# TX.net
KiCad netlist of a schematic drawn in EAGLE
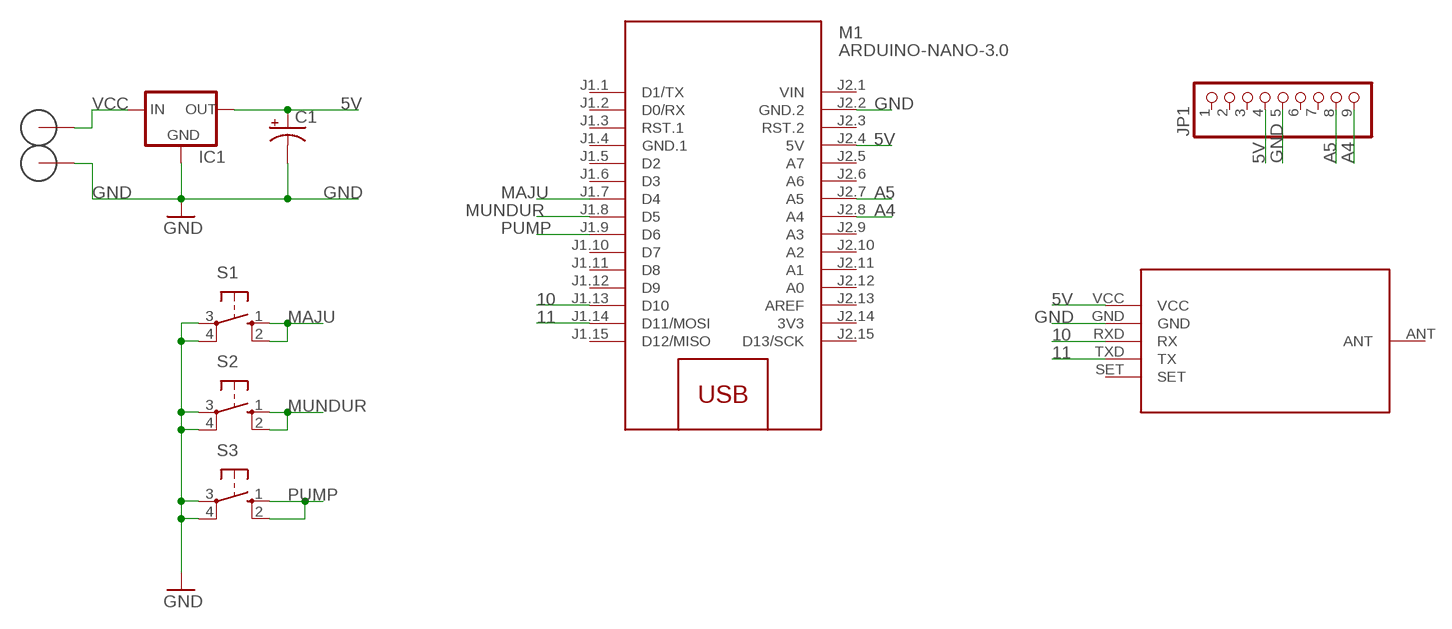
[diagram p0: schematic, sheet 1]

(export (version "E")
  (design (tool "Eeschema 10.0.6"))
  (components
    (comp (ref "C1")
      (value "CPOL-USE2.5-7")
      (footprint "eagle-import:E2,5-7")
      (libsource (lib "eagle-import") (part "CPOL-USE2.5-7"))
    )
    (comp (ref "H1")
      (value "3MM_HOLE")
      (footprint "eagle-import:3MM_HOLE")
      (libsource (lib "eagle-import") (part "3MM_HOLE"))
    )
    (comp (ref "H2")
      (value "3MM_HOLE")
      (footprint "eagle-import:3MM_HOLE")
      (libsource (lib "eagle-import") (part "3MM_HOLE"))
    )
    (comp (ref "IC1")
      (value "78XXS")
      (footprint "eagle-import:78XXS")
      (libsource (lib "eagle-import") (part "78XXS"))
    )
    (comp (ref "JP1")
      (value "PINHD-1X9")
      (footprint "eagle-import:1X09")
      (libsource (lib "eagle-import") (part "PINHD-1X9"))
    )
    (comp (ref "M1")
      (value "ARDUINO-NANO-3.0")
      (footprint "eagle-import:ARDUINO-NANO-3.0")
      (libsource (lib "eagle-import") (part "ARDUINO-NANO-3.0"))
    )
    (comp (ref "S1")
      (value "10-XX")
      (footprint "eagle-import:B3F-10XX")
      (fields (field (name "MPN") "B3F-1000"))
      (libsource (lib "eagle-import") (part "10-XX"))
    )
    (comp (ref "S2")
      (value "10-XX")
      (footprint "eagle-import:B3F-10XX")
      (fields (field (name "MPN") "B3F-1000"))
      (libsource (lib "eagle-import") (part "10-XX"))
    )
    (comp (ref "S3")
      (value "10-XX")
      (footprint "eagle-import:B3F-10XX")
      (fields (field (name "MPN") "B3F-1000"))
      (libsource (lib "eagle-import") (part "10-XX"))
    )
    (comp (ref "U$1")
      (value "HC-12_FOOTPRINT")
      (footprint "eagle-import:HC-12_FOOTPRINT")
      (libsource (lib "eagle-import") (part "HC-12_FOOTPRINT"))
    )
  )
  (nets
    (net (code "1") (name "/3V3") (class "Default")
      (node (ref "M1") (pin "J2.14") (pinfunction "3V3_J2.14") (pintype "power_in"))
    )
    (net (code "2") (name "/5V") (class "Default")
      (node (ref "C1") (pin "+") (pinfunction "+_+") (pintype "passive"))
      (node (ref "IC1") (pin "OUT") (pinfunction "OUT_OUT") (pintype "passive"))
      (node (ref "JP1") (pin "4") (pinfunction "4_4") (pintype "passive"))
      (node (ref "M1") (pin "J2.4") (pinfunction "5V_J2.4") (pintype "power_in"))
      (node (ref "U$1") (pin "VCC") (pinfunction "VCC_VCC") (pintype "bidirectional"))
    )
    (net (code "3") (name "/10") (class "Default")
      (node (ref "M1") (pin "J1.13") (pinfunction "D10_J1.13") (pintype "bidirectional"))
      (node (ref "U$1") (pin "RXD") (pinfunction "RX_RXD") (pintype "bidirectional"))
    )
    (net (code "4") (name "/11") (class "Default")
      (node (ref "M1") (pin "J1.14") (pinfunction "D11/MOSI_J1.14") (pintype "bidirectional"))
      (node (ref "U$1") (pin "TXD") (pinfunction "TX_TXD") (pintype "bidirectional"))
    )
    (net (code "5") (name "/A4") (class "Default")
      (node (ref "JP1") (pin "9") (pinfunction "9_9") (pintype "passive"))
      (node (ref "M1") (pin "J2.8") (pinfunction "A4_J2.8") (pintype "bidirectional"))
    )
    (net (code "6") (name "/A5") (class "Default")
      (node (ref "JP1") (pin "8") (pinfunction "8_8") (pintype "passive"))
      (node (ref "M1") (pin "J2.7") (pinfunction "A5_J2.7") (pintype "bidirectional"))
    )
    (net (code "7") (name "/GND.1") (class "Default")
      (node (ref "M1") (pin "J1.4") (pinfunction "GND.1_J1.4") (pintype "power_in"))
    )
    (net (code "8") (name "/MAJU") (class "Default")
      (node (ref "M1") (pin "J1.7") (pinfunction "D4_J1.7") (pintype "bidirectional"))
      (node (ref "S1") (pin "1") (pinfunction "S_1") (pintype "passive"))
      (node (ref "S1") (pin "2") (pinfunction "S1_2") (pintype "passive"))
    )
    (net (code "9") (name "/MUNDUR") (class "Default")
      (node (ref "M1") (pin "J1.8") (pinfunction "D5_J1.8") (pintype "bidirectional"))
      (node (ref "S2") (pin "1") (pinfunction "S_1") (pintype "passive"))
      (node (ref "S2") (pin "2") (pinfunction "S1_2") (pintype "passive"))
    )
    (net (code "10") (name "/PUMP") (class "Default")
      (node (ref "M1") (pin "J1.9") (pinfunction "D6_J1.9") (pintype "bidirectional"))
      (node (ref "S3") (pin "1") (pinfunction "S_1") (pintype "passive"))
      (node (ref "S3") (pin "2") (pinfunction "S1_2") (pintype "passive"))
    )
    (net (code "11") (name "/VCC") (class "Default")
      (node (ref "H1") (pin "P$1") (pinfunction "GND_P$1") (pintype "bidirectional"))
      (node (ref "H1") (pin "P$2") (pinfunction "GND_P$2") (pintype "bidirectional"))
      (node (ref "H1") (pin "P$3") (pinfunction "GND_P$3") (pintype "bidirectional"))
      (node (ref "H1") (pin "P$4") (pinfunction "GND_P$4") (pintype "bidirectional"))
      (node (ref "H1") (pin "P$5") (pinfunction "GND_P$5") (pintype "bidirectional"))
      (node (ref "H1") (pin "P$6") (pinfunction "GND_P$6") (pintype "bidirectional"))
      (node (ref "H1") (pin "P$7") (pinfunction "GND_P$7") (pintype "bidirectional"))
      (node (ref "H1") (pin "P$8") (pinfunction "GND_P$8") (pintype "bidirectional"))
      (node (ref "H1") (pin "P$9") (pinfunction "GND_P$9") (pintype "bidirectional"))
      (node (ref "IC1") (pin "IN") (pinfunction "IN_IN") (pintype "input"))
    )
    (net (code "12") (name "/VIN") (class "Default")
      (node (ref "M1") (pin "J2.1") (pinfunction "VIN_J2.1") (pintype "power_in"))
    )
    (net (code "13") (name "GND") (class "Default")
      (node (ref "C1") (pin "-") (pinfunction "-_-") (pintype "passive"))
      (node (ref "H2") (pin "P$1") (pinfunction "GND_P$1") (pintype "bidirectional"))
      (node (ref "H2") (pin "P$2") (pinfunction "GND_P$2") (pintype "bidirectional"))
      (node (ref "H2") (pin "P$3") (pinfunction "GND_P$3") (pintype "bidirectional"))
      (node (ref "H2") (pin "P$4") (pinfunction "GND_P$4") (pintype "bidirectional"))
      (node (ref "H2") (pin "P$5") (pinfunction "GND_P$5") (pintype "bidirectional"))
      (node (ref "H2") (pin "P$6") (pinfunction "GND_P$6") (pintype "bidirectional"))
      (node (ref "H2") (pin "P$7") (pinfunction "GND_P$7") (pintype "bidirectional"))
      (node (ref "H2") (pin "P$8") (pinfunction "GND_P$8") (pintype "bidirectional"))
      (node (ref "H2") (pin "P$9") (pinfunction "GND_P$9") (pintype "bidirectional"))
      (node (ref "IC1") (pin "GND") (pinfunction "GND_GND") (pintype "input"))
      (node (ref "JP1") (pin "5") (pinfunction "5_5") (pintype "passive"))
      (node (ref "M1") (pin "J2.2") (pinfunction "GND.2_J2.2") (pintype "power_in"))
      (node (ref "S1") (pin "3") (pinfunction "P_3") (pintype "passive"))
      (node (ref "S1") (pin "4") (pinfunction "P1_4") (pintype "passive"))
      (node (ref "S2") (pin "3") (pinfunction "P_3") (pintype "passive"))
      (node (ref "S2") (pin "4") (pinfunction "P1_4") (pintype "passive"))
      (node (ref "S3") (pin "3") (pinfunction "P_3") (pintype "passive"))
      (node (ref "S3") (pin "4") (pinfunction "P1_4") (pintype "passive"))
      (node (ref "U$1") (pin "GND") (pinfunction "GND_GND") (pintype "bidirectional"))
    )
    (net (code "14") (name "unconnected-(JP1-Pad1)") (class "Default")
      (node (ref "JP1") (pin "1") (pinfunction "1_1") (pintype "passive"))
    )
    (net (code "15") (name "unconnected-(JP1-Pad2)") (class "Default")
      (node (ref "JP1") (pin "2") (pinfunction "2_2") (pintype "passive"))
    )
    (net (code "16") (name "unconnected-(JP1-Pad3)") (class "Default")
      (node (ref "JP1") (pin "3") (pinfunction "3_3") (pintype "passive"))
    )
    (net (code "17") (name "unconnected-(JP1-Pad6)") (class "Default")
      (node (ref "JP1") (pin "6") (pinfunction "6_6") (pintype "passive"))
    )
    (net (code "18") (name "unconnected-(JP1-Pad7)") (class "Default")
      (node (ref "JP1") (pin "7") (pinfunction "7_7") (pintype "passive"))
    )
    (net (code "19") (name "unconnected-(M1-A0-PadJ2.12)") (class "Default")
      (node (ref "M1") (pin "J2.12") (pinfunction "A0_J2.12") (pintype "bidirectional"))
    )
    (net (code "20") (name "unconnected-(M1-A1-PadJ2.11)") (class "Default")
      (node (ref "M1") (pin "J2.11") (pinfunction "A1_J2.11") (pintype "bidirectional"))
    )
    (net (code "21") (name "unconnected-(M1-A2-PadJ2.10)") (class "Default")
      (node (ref "M1") (pin "J2.10") (pinfunction "A2_J2.10") (pintype "bidirectional"))
    )
    (net (code "22") (name "unconnected-(M1-A3-PadJ2.9)") (class "Default")
      (node (ref "M1") (pin "J2.9") (pinfunction "A3_J2.9") (pintype "bidirectional"))
    )
    (net (code "23") (name "unconnected-(M1-A6-PadJ2.6)") (class "Default")
      (node (ref "M1") (pin "J2.6") (pinfunction "A6_J2.6") (pintype "bidirectional"))
    )
    (net (code "24") (name "unconnected-(M1-A7-PadJ2.5)") (class "Default")
      (node (ref "M1") (pin "J2.5") (pinfunction "A7_J2.5") (pintype "bidirectional"))
    )
    (net (code "25") (name "unconnected-(M1-AREF-PadJ2.13)") (class "Default")
      (node (ref "M1") (pin "J2.13") (pinfunction "AREF_J2.13") (pintype "bidirectional"))
    )
    (net (code "26") (name "unconnected-(M1-D0{slash}RX-PadJ1.2)") (class "Default")
      (node (ref "M1") (pin "J1.2") (pinfunction "D0/RX_J1.2") (pintype "bidirectional"))
    )
    (net (code "27") (name "unconnected-(M1-D1{slash}TX-PadJ1.1)") (class "Default")
      (node (ref "M1") (pin "J1.1") (pinfunction "D1/TX_J1.1") (pintype "bidirectional"))
    )
    (net (code "28") (name "unconnected-(M1-D2-PadJ1.5)") (class "Default")
      (node (ref "M1") (pin "J1.5") (pinfunction "D2_J1.5") (pintype "bidirectional"))
    )
    (net (code "29") (name "unconnected-(M1-D3-PadJ1.6)") (class "Default")
      (node (ref "M1") (pin "J1.6") (pinfunction "D3_J1.6") (pintype "bidirectional"))
    )
    (net (code "30") (name "unconnected-(M1-D7-PadJ1.10)") (class "Default")
      (node (ref "M1") (pin "J1.10") (pinfunction "D7_J1.10") (pintype "bidirectional"))
    )
    (net (code "31") (name "unconnected-(M1-D8-PadJ1.11)") (class "Default")
      (node (ref "M1") (pin "J1.11") (pinfunction "D8_J1.11") (pintype "bidirectional"))
    )
    (net (code "32") (name "unconnected-(M1-D9-PadJ1.12)") (class "Default")
      (node (ref "M1") (pin "J1.12") (pinfunction "D9_J1.12") (pintype "bidirectional"))
    )
    (net (code "33") (name "unconnected-(M1-D12{slash}MISO-PadJ1.15)") (class "Default")
      (node (ref "M1") (pin "J1.15") (pinfunction "D12/MISO_J1.15") (pintype "bidirectional"))
    )
    (net (code "34") (name "unconnected-(M1-D13{slash}SCK-PadJ2.15)") (class "Default")
      (node (ref "M1") (pin "J2.15") (pinfunction "D13/SCK_J2.15") (pintype "bidirectional"))
    )
    (net (code "35") (name "unconnected-(M1-RST.1-PadJ1.3)") (class "Default")
      (node (ref "M1") (pin "J1.3") (pinfunction "RST.1_J1.3") (pintype "bidirectional"))
    )
    (net (code "36") (name "unconnected-(M1-RST.2-PadJ2.3)") (class "Default")
      (node (ref "M1") (pin "J2.3") (pinfunction "RST.2_J2.3") (pintype "bidirectional"))
    )
    (net (code "37") (name "unconnected-(U$1-PadANT)") (class "Default")
      (node (ref "U$1") (pin "ANT") (pinfunction "ANT_ANT") (pintype "bidirectional"))
    )
    (net (code "38") (name "unconnected-(U$1-PadSET)") (class "Default")
      (node (ref "U$1") (pin "SET") (pinfunction "SET_SET") (pintype "bidirectional"))
    )
  )
)
